# 04_RGB_LED_Driver.net
KiCad netlist of a schematic drawn in Altium Designer
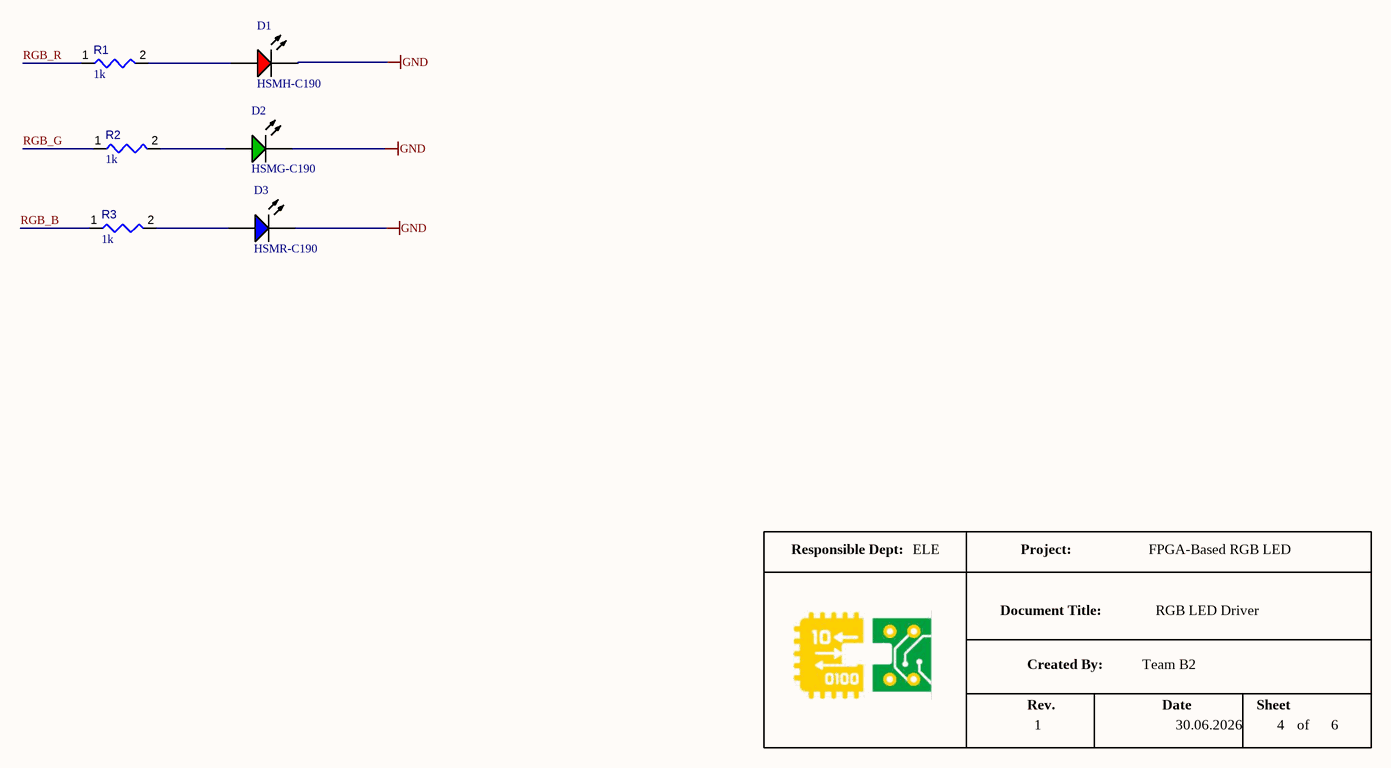
[diagram p0: 04_RGB_LED_Driver.SchDoc]

(export (version "E")
  (design (tool "Eeschema 10.0.6"))
  (components
    (comp (ref "D1")
      (value "HSMH-C190")
      (footprint "AVAG-HSMX-C190_V")
      (description "LED Uni-Color Red, 65 mW, 20 mA, -40 to 85 degC, 2-Pin SMD, RoHS, Tape and Reel")
      (fields (field (name "POWER") "78mW") (field (name "MANUFACTURER") "Avago"))
      (libsource (lib "Hany Chowdhury") (part "LED-RED-AK-2"))
    )
    (comp (ref "D2")
      (value "HSMG-C190")
      (footprint "AVAG-HSMX-C190_V")
      (description "LED Uni-Color Green, 52 mW, 20 mA, -40 to 85 degC, 2-Pin SMD, RoHS, Tape and Reel")
      (fields (field (name "POWER") "52mW") (field (name "MANUFACTURER") "Avago"))
      (libsource (lib "Hany Chowdhury") (part "LED-GREEN-AK-2"))
    )
    (comp (ref "D3")
      (value "HSMR-C190")
      (footprint "AVAG-HSMX-C190_V")
      (description "LED Uni-Color Blue, 78 mW, 20 mA, -40 to 85 degC, 2-Pin SMD, RoHS, Tape and Reel")
      (fields (field (name "POWER") "78mW") (field (name "MANUFACTURER") "Avago"))
      (libsource (lib "Hany Chowdhury") (part "LED-BLUE-AK-2"))
    )
    (comp (ref "R1")
      (value "1k")
      (footprint "RESC0805(2012)_L")
      (description "1K 0.125W 5% 0805 (2012 Metric)  SMD")
      (fields (field (name "TOLERANCE") "5%") (field (name "POWER") "125mW"))
      (libsource (lib "Hany Chowdhury") (part "1KR5J"))
    )
    (comp (ref "R2")
      (value "1k")
      (footprint "RESC0805(2012)_L")
      (description "1K 0.125W 5% 0805 (2012 Metric)  SMD")
      (fields (field (name "TOLERANCE") "5%") (field (name "POWER") "125mW"))
      (libsource (lib "Hany Chowdhury") (part "1KR5J"))
    )
    (comp (ref "R3")
      (value "1k")
      (footprint "RESC0805(2012)_L")
      (description "1K 0.125W 5% 0805 (2012 Metric)  SMD")
      (fields (field (name "TOLERANCE") "5%") (field (name "POWER") "125mW"))
      (libsource (lib "Hany Chowdhury") (part "1KR5J"))
    )
  )
  (nets
    (net (code "1") (name "/RGB_B") (class "Default")
      (node (ref "R3") (pin "1") (pinfunction "1_1") (pintype "passive"))
    )
    (net (code "2") (name "/RGB_G") (class "Default")
      (node (ref "R2") (pin "1") (pinfunction "1_1") (pintype "passive"))
    )
    (net (code "3") (name "/RGB_R") (class "Default")
      (node (ref "R1") (pin "1") (pinfunction "1_1") (pintype "passive"))
    )
    (net (code "4") (name "GND") (class "Default")
      (node (ref "D1") (pin "2") (pinfunction "K_2") (pintype "passive"))
      (node (ref "D2") (pin "2") (pinfunction "K_2") (pintype "passive"))
      (node (ref "D3") (pin "2") (pinfunction "K_2") (pintype "passive"))
    )
    (net (code "5") (name "Net-(D1-A)") (class "Default")
      (node (ref "D1") (pin "1") (pinfunction "A_1") (pintype "passive"))
      (node (ref "R1") (pin "2") (pinfunction "2_2") (pintype "passive"))
    )
    (net (code "6") (name "Net-(D2-A)") (class "Default")
      (node (ref "D2") (pin "1") (pinfunction "A_1") (pintype "passive"))
      (node (ref "R2") (pin "2") (pinfunction "2_2") (pintype "passive"))
    )
    (net (code "7") (name "Net-(D3-A)") (class "Default")
      (node (ref "D3") (pin "1") (pinfunction "A_1") (pintype "passive"))
      (node (ref "R3") (pin "2") (pinfunction "2_2") (pintype "passive"))
    )
  )
)
